# assgn2.net
KiCad netlist of a schematic drawn in EAGLE
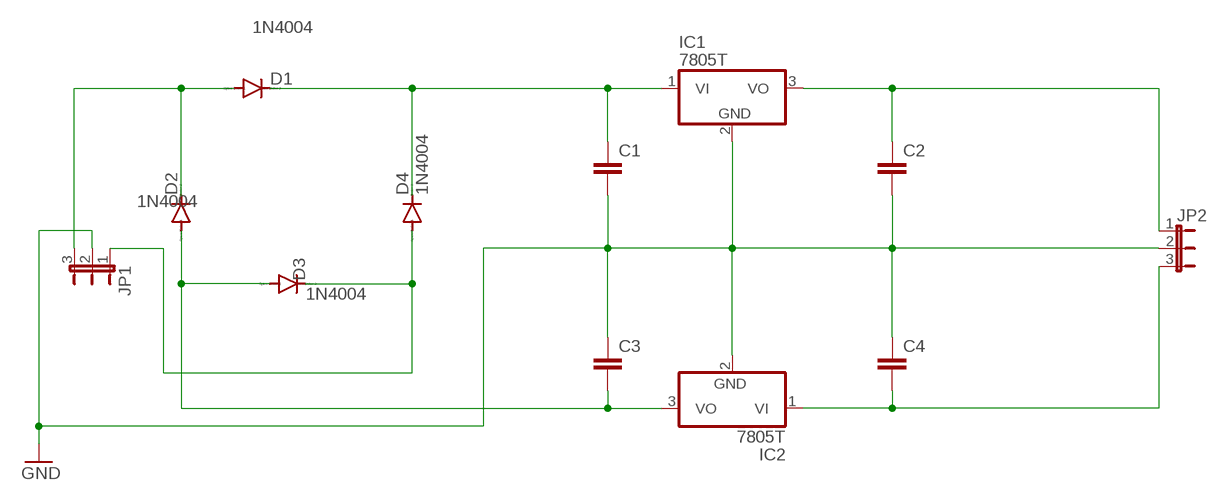
[diagram p0: schematic, sheet 1]

(export (version "E")
  (design (tool "Eeschema 10.0.6"))
  (components
    (comp (ref "C1")
      (value "C2,5-3")
      (footprint "eagle-import:C2.5-3")
      (libsource (lib "eagle-import") (part "C2,5-3"))
    )
    (comp (ref "C2")
      (value "C2,5-3")
      (footprint "eagle-import:C2.5-3")
      (libsource (lib "eagle-import") (part "C2,5-3"))
    )
    (comp (ref "C3")
      (value "C2,5-3")
      (footprint "eagle-import:C2.5-3")
      (libsource (lib "eagle-import") (part "C2,5-3"))
    )
    (comp (ref "C4")
      (value "C2,5-3")
      (footprint "eagle-import:C2.5-3")
      (libsource (lib "eagle-import") (part "C2,5-3"))
    )
    (comp (ref "D1")
      (value "1N4004")
      (footprint "eagle-import:DO41-10")
      (libsource (lib "eagle-import") (part "1N4004"))
    )
    (comp (ref "D2")
      (value "1N4004")
      (footprint "eagle-import:DO41-10")
      (libsource (lib "eagle-import") (part "1N4004"))
    )
    (comp (ref "D3")
      (value "1N4004")
      (footprint "eagle-import:DO41-10")
      (libsource (lib "eagle-import") (part "1N4004"))
    )
    (comp (ref "D4")
      (value "1N4004")
      (footprint "eagle-import:DO41-10")
      (libsource (lib "eagle-import") (part "1N4004"))
    )
    (comp (ref "IC1")
      (value "7805T")
      (footprint "eagle-import:TO220H")
      (libsource (lib "eagle-import") (part "78T05"))
    )
    (comp (ref "IC2")
      (value "7805T")
      (footprint "eagle-import:TO220H")
      (libsource (lib "eagle-import") (part "78T05"))
    )
    (comp (ref "JP1")
      (value "JP2E")
      (footprint "eagle-import:JP2")
      (libsource (lib "eagle-import") (part "JP2E"))
    )
    (comp (ref "JP2")
      (value "JP2E")
      (footprint "eagle-import:JP2")
      (libsource (lib "eagle-import") (part "JP2E"))
    )
  )
  (nets
    (net (code "1") (name "GND") (class "Default")
      (node (ref "C1") (pin "2") (pinfunction "2_2") (pintype "passive"))
      (node (ref "C2") (pin "2") (pinfunction "2_2") (pintype "passive"))
      (node (ref "C3") (pin "1") (pinfunction "1_1") (pintype "passive"))
      (node (ref "C4") (pin "1") (pinfunction "1_1") (pintype "passive"))
      (node (ref "IC1") (pin "2") (pinfunction "GND_2") (pintype "passive"))
      (node (ref "IC2") (pin "2") (pinfunction "GND_2") (pintype "passive"))
      (node (ref "JP1") (pin "2") (pinfunction "2_2") (pintype "passive"))
      (node (ref "JP2") (pin "2") (pinfunction "2_2") (pintype "passive"))
    )
    (net (code "2") (name "Net-(D1-PadA)") (class "Default")
      (node (ref "D1") (pin "A") (pinfunction "A_A") (pintype "passive"))
      (node (ref "D2") (pin "C") (pinfunction "C_C") (pintype "passive"))
      (node (ref "JP1") (pin "3") (pinfunction "3_3") (pintype "passive"))
    )
    (net (code "3") (name "Net-(D3-PadC)") (class "Default")
      (node (ref "D3") (pin "C") (pinfunction "C_C") (pintype "passive"))
      (node (ref "D4") (pin "A") (pinfunction "A_A") (pintype "passive"))
      (node (ref "JP1") (pin "1") (pinfunction "1_1") (pintype "passive"))
    )
    (net (code "4") (name "Net-(IC1-VI)") (class "Default")
      (node (ref "C1") (pin "1") (pinfunction "1_1") (pintype "passive"))
      (node (ref "D1") (pin "C") (pinfunction "C_C") (pintype "passive"))
      (node (ref "D4") (pin "C") (pinfunction "C_C") (pintype "passive"))
      (node (ref "IC1") (pin "1") (pinfunction "VI_1") (pintype "input"))
    )
    (net (code "5") (name "Net-(IC1-VO)") (class "Default")
      (node (ref "C2") (pin "1") (pinfunction "1_1") (pintype "passive"))
      (node (ref "IC1") (pin "3") (pinfunction "VO_3") (pintype "passive"))
      (node (ref "JP2") (pin "1") (pinfunction "1_1") (pintype "passive"))
    )
    (net (code "6") (name "Net-(IC2-VI)") (class "Default")
      (node (ref "C4") (pin "2") (pinfunction "2_2") (pintype "passive"))
      (node (ref "IC2") (pin "1") (pinfunction "VI_1") (pintype "input"))
      (node (ref "JP2") (pin "3") (pinfunction "3_3") (pintype "passive"))
    )
    (net (code "7") (name "Net-(IC2-VO)") (class "Default")
      (node (ref "C3") (pin "2") (pinfunction "2_2") (pintype "passive"))
      (node (ref "D2") (pin "A") (pinfunction "A_A") (pintype "passive"))
      (node (ref "D3") (pin "A") (pinfunction "A_A") (pintype "passive"))
      (node (ref "IC2") (pin "3") (pinfunction "VO_3") (pintype "passive"))
    )
  )
)
